# Regulador.net
KiCad netlist of a schematic drawn in Altium Designer
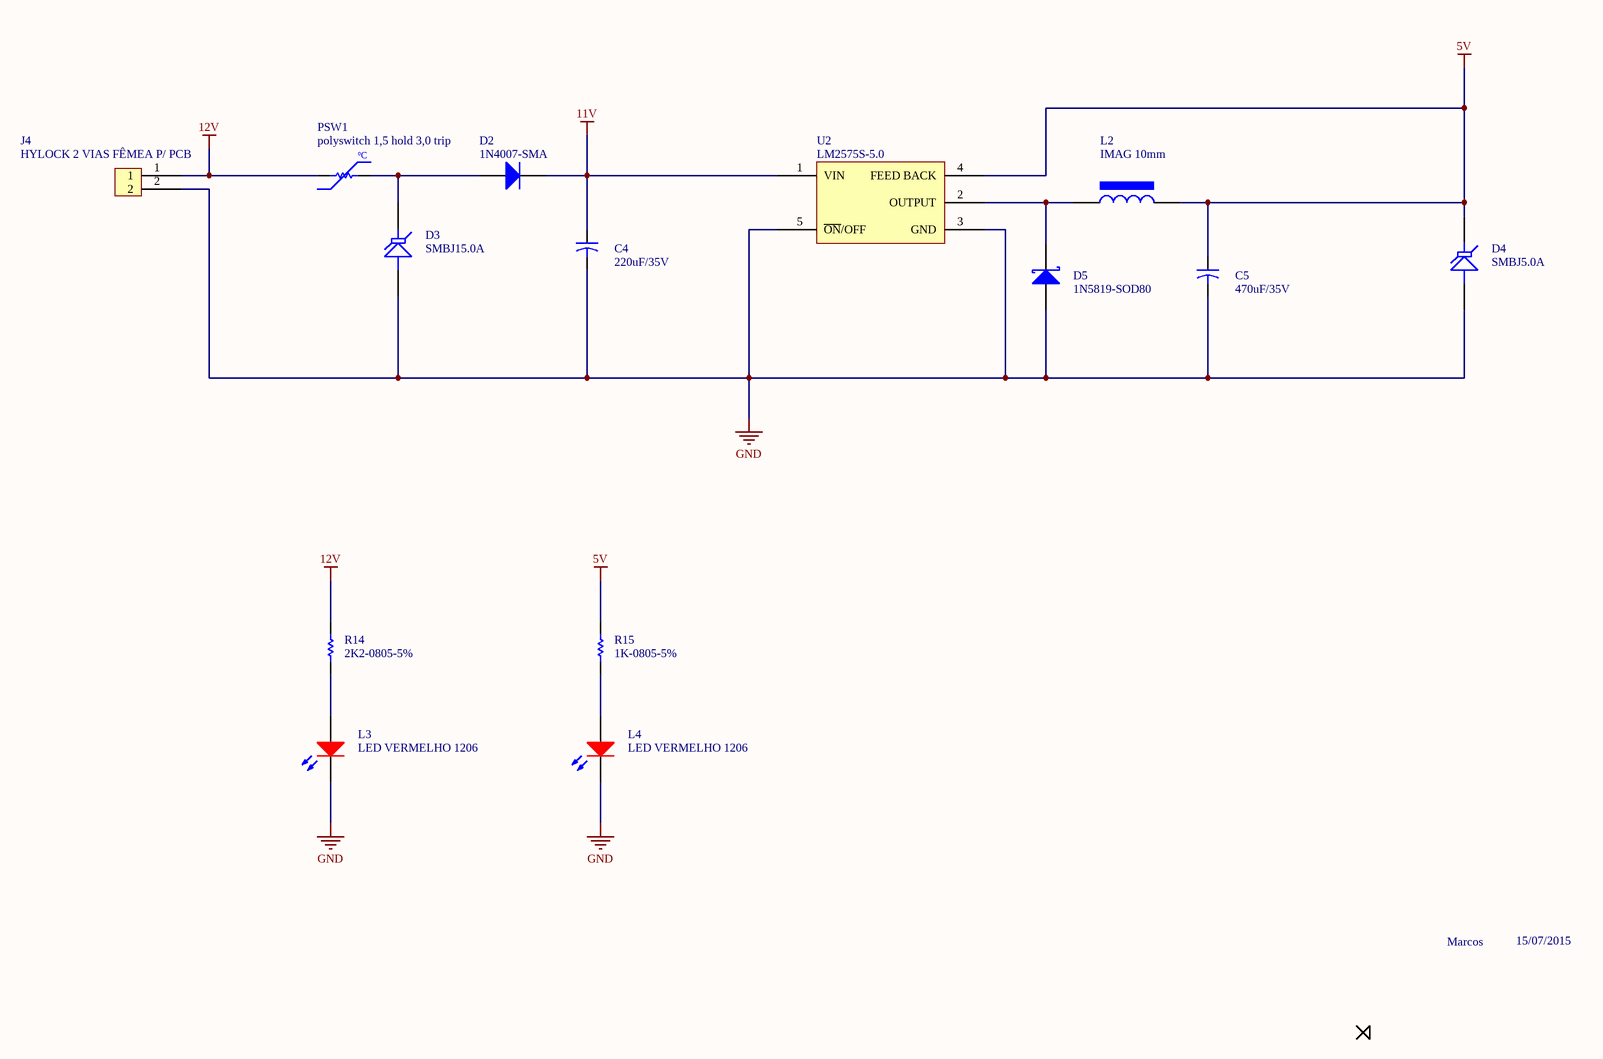
[diagram p0: Regulador.SchDoc]

(export (version "E")
  (design (tool "Eeschema 10.0.6"))
  (components
    (comp (ref "C4")
      (value "220uF/35V")
      (footprint "CAP POL 8x12mm")
      (description "2200uF/50V")
      (libsource (lib "AquinoLib") (part "2200uF/50V"))
    )
    (comp (ref "C5")
      (value "470uF/35V")
      (footprint "CAP POL 8x12mm")
      (description "470uF/50V")
      (libsource (lib "AquinoLib") (part "470uF/50V"))
    )
    (comp (ref "D2")
      (value "1N4007-SMA")
      (footprint "SMA DIODES")
      (description "1N4007")
      (libsource (lib "AquinoLib") (part "1N4007"))
    )
    (comp (ref "D3")
      (value "SMBJ15.0A")
      (footprint "SMA DIODES")
      (description "SMBJ30.0A")
      (libsource (lib "AquinoLib") (part "SMBJ30.0A"))
    )
    (comp (ref "D4")
      (value "SMBJ5.0A")
      (footprint "SMA DIODES")
      (libsource (lib "AquinoLib") (part "SMBJ5.0A"))
    )
    (comp (ref "D5")
      (value "1N5819-SOD80")
      (footprint "SMA DIODES")
      (libsource (lib "AquinoLib") (part "1N5819-SOD80"))
    )
    (comp (ref "J4")
      (value "HYLOCK 2 VIAS FÊMEA P/ PCB")
      (footprint "CONECTOR HYLOCK 2 VIAS")
      (description "PCMC2-2")
      (libsource (lib "AquinoLib") (part "PCMC2-2"))
    )
    (comp (ref "L2")
      (value "IMAG 10mm")
      (footprint "INDUTOR 47mH")
      (description "1mH-CNF15-26 AWG")
      (libsource (lib "AquinoLib") (part "indutor 1mH CNF15"))
    )
    (comp (ref "L3")
      (value "LED VERMELHO 1206")
      (footprint "LED 1206")
      (description "LED VERMELHO 5mm")
      (libsource (lib "AquinoLib") (part "LED VERMELHO 5mm"))
    )
    (comp (ref "L4")
      (value "LED VERMELHO 1206")
      (footprint "LED 1206")
      (description "LED VERMELHO 5mm")
      (libsource (lib "AquinoLib") (part "LED VERMELHO 5mm"))
    )
    (comp (ref "PSW1")
      (value "polyswitch 1,5 hold 3,0 trip")
      (footprint "1206-REVISADO ONDA")
      (description "NANOSMDC020F-2")
      (libsource (lib "AquinoLib") (part "POLYSWITCH 200mA"))
    )
    (comp (ref "R14")
      (value "2K2-0805-5%")
      (footprint "0805-REVISADO ONDA")
      (description "1K-0805-5%")
      (libsource (lib "AquinoLib") (part "1K-0805-5%"))
    )
    (comp (ref "R15")
      (value "1K-0805-5%")
      (footprint "0805-REVISADO ONDA")
      (libsource (lib "AquinoLib") (part "1K-0805-5%"))
    )
    (comp (ref "U2")
      (value "LM2575S-5.0")
      (footprint "TO-263-5")
      (description "LM2596S-ADJ")
      (libsource (lib "AquinoLib") (part "LM2596S-ADJ"))
    )
  )
  (nets
    (net (code "1") (name "5V") (class "Default")
      (node (ref "C5") (pin "1") (pinfunction "1_1") (pintype "passive"))
      (node (ref "D4") (pin "2") (pinfunction "K_2") (pintype "passive"))
      (node (ref "L2") (pin "1") (pinfunction "1_1") (pintype "passive"))
      (node (ref "R15") (pin "2") (pinfunction "2_2") (pintype "passive"))
      (node (ref "U2") (pin "4") (pinfunction "FEED_BACK_4") (pintype "passive"))
    )
    (net (code "2") (name "11V") (class "Default")
      (node (ref "C4") (pin "1") (pinfunction "1_1") (pintype "passive"))
      (node (ref "D2") (pin "2") (pinfunction "K_2") (pintype "passive"))
      (node (ref "U2") (pin "1") (pinfunction "VIN_1") (pintype "passive"))
    )
    (net (code "3") (name "12V") (class "Default")
      (node (ref "J4") (pin "1") (pinfunction "1_1") (pintype "passive"))
      (node (ref "PSW1") (pin "1") (pinfunction "1_1") (pintype "passive"))
      (node (ref "R14") (pin "2") (pinfunction "2_2") (pintype "passive"))
    )
    (net (code "4") (name "GND") (class "Default")
      (node (ref "C4") (pin "2") (pinfunction "2_2") (pintype "passive"))
      (node (ref "C5") (pin "2") (pinfunction "2_2") (pintype "passive"))
      (node (ref "D3") (pin "1") (pinfunction "A_1") (pintype "passive"))
      (node (ref "D4") (pin "1") (pinfunction "A_1") (pintype "passive"))
      (node (ref "D5") (pin "1") (pinfunction "A_1") (pintype "passive"))
      (node (ref "J4") (pin "2") (pinfunction "2_2") (pintype "passive"))
      (node (ref "L3") (pin "2") (pinfunction "K_2") (pintype "passive"))
      (node (ref "L4") (pin "2") (pinfunction "K_2") (pintype "passive"))
      (node (ref "U2") (pin "3") (pinfunction "GND_3") (pintype "passive"))
      (node (ref "U2") (pin "5") (pinfunction "~{ON}/OFF_5") (pintype "passive"))
    )
    (net (code "5") (name "Net-(D2-A)") (class "Default")
      (node (ref "D2") (pin "1") (pinfunction "A_1") (pintype "passive"))
      (node (ref "D3") (pin "2") (pinfunction "K_2") (pintype "passive"))
      (node (ref "PSW1") (pin "2") (pinfunction "2_2") (pintype "passive"))
    )
    (net (code "6") (name "Net-(D5-K)") (class "Default")
      (node (ref "D5") (pin "2") (pinfunction "K_2") (pintype "passive"))
      (node (ref "L2") (pin "2") (pinfunction "2_2") (pintype "passive"))
      (node (ref "U2") (pin "2") (pinfunction "OUTPUT_2") (pintype "passive"))
    )
    (net (code "7") (name "Net-(L3-A)") (class "Default")
      (node (ref "L3") (pin "1") (pinfunction "A_1") (pintype "passive"))
      (node (ref "R14") (pin "1") (pinfunction "1_1") (pintype "passive"))
    )
    (net (code "8") (name "Net-(L4-A)") (class "Default")
      (node (ref "L4") (pin "1") (pinfunction "A_1") (pintype "passive"))
      (node (ref "R15") (pin "1") (pinfunction "1_1") (pintype "passive"))
    )
  )
)
